# power_supply.net
KiCad netlist of a schematic drawn in EAGLE
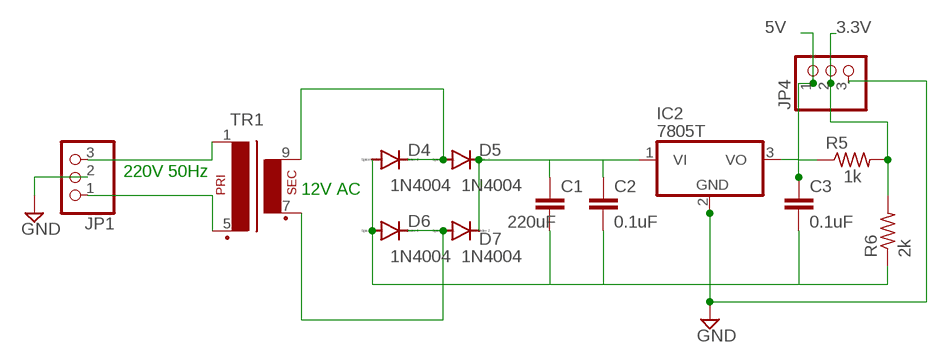
[diagram p0: schematic, sheet 1]

(export (version "E")
  (design (tool "Eeschema 10.0.6"))
  (components
    (comp (ref "C1")
      (value "220uF")
      (footprint "eagle-import:C050-025X075")
      (libsource (lib "eagle-import") (part "C-EU050-025X075"))
    )
    (comp (ref "C2")
      (value "0.1uF")
      (footprint "eagle-import:C050-025X075")
      (libsource (lib "eagle-import") (part "C-EU050-025X075"))
    )
    (comp (ref "C3")
      (value "0.1uF")
      (footprint "eagle-import:C050-025X075")
      (libsource (lib "eagle-import") (part "C-EU050-025X075"))
    )
    (comp (ref "D4")
      (value "1N4004")
      (footprint "eagle-import:DO41-10")
      (libsource (lib "eagle-import") (part "1N4004"))
    )
    (comp (ref "D5")
      (value "1N4004")
      (footprint "eagle-import:DO41-10")
      (libsource (lib "eagle-import") (part "1N4004"))
    )
    (comp (ref "D6")
      (value "1N4004")
      (footprint "eagle-import:DO41-10")
      (libsource (lib "eagle-import") (part "1N4004"))
    )
    (comp (ref "D7")
      (value "1N4004")
      (footprint "eagle-import:DO41-10")
      (libsource (lib "eagle-import") (part "1N4004"))
    )
    (comp (ref "IC2")
      (value "7805T")
      (footprint "eagle-import:TO220H")
      (libsource (lib "eagle-import") (part "78T05"))
    )
    (comp (ref "JP1")
      (value "PINHD-1X3")
      (footprint "eagle-import:1X03")
      (libsource (lib "eagle-import") (part "PINHD-1X3"))
    )
    (comp (ref "JP4")
      (value "PINHD-1X3")
      (footprint "eagle-import:1X03")
      (libsource (lib "eagle-import") (part "PINHD-1X3"))
    )
    (comp (ref "R5")
      (value "1k")
      (footprint "eagle-import:0207_10")
      (libsource (lib "eagle-import") (part "R-US_0207/10"))
    )
    (comp (ref "R6")
      (value "2k")
      (footprint "eagle-import:0207_10")
      (libsource (lib "eagle-import") (part "R-US_0207/10"))
    )
    (comp (ref "TR1")
      (value "EI30-1")
      (footprint "eagle-import:EI30-1")
      (libsource (lib "eagle-import") (part "EI30-1"))
    )
  )
  (nets
    (net (code "1") (name "/3.3V") (class "Default")
      (node (ref "JP4") (pin "2") (pinfunction "2_2") (pintype "passive"))
      (node (ref "R5") (pin "2") (pinfunction "2_2") (pintype "passive"))
      (node (ref "R6") (pin "2") (pinfunction "2_2") (pintype "passive"))
    )
    (net (code "2") (name "/5V") (class "Default")
      (node (ref "C3") (pin "1") (pinfunction "1_1") (pintype "passive"))
      (node (ref "IC2") (pin "3") (pinfunction "VO_3") (pintype "passive"))
      (node (ref "JP4") (pin "1") (pinfunction "1_1") (pintype "passive"))
      (node (ref "R5") (pin "1") (pinfunction "1_1") (pintype "passive"))
    )
    (net (code "3") (name "GND") (class "Default")
      (node (ref "C1") (pin "2") (pinfunction "2_2") (pintype "passive"))
      (node (ref "C2") (pin "2") (pinfunction "2_2") (pintype "passive"))
      (node (ref "C3") (pin "2") (pinfunction "2_2") (pintype "passive"))
      (node (ref "D4") (pin "A") (pinfunction "A_A") (pintype "passive"))
      (node (ref "D6") (pin "A") (pinfunction "A_A") (pintype "passive"))
      (node (ref "IC2") (pin "2") (pinfunction "GND_2") (pintype "passive"))
      (node (ref "JP1") (pin "2") (pinfunction "2_2") (pintype "passive"))
      (node (ref "JP4") (pin "3") (pinfunction "3_3") (pintype "passive"))
      (node (ref "R6") (pin "1") (pinfunction "1_1") (pintype "passive"))
    )
    (net (code "4") (name "Net-(IC2-VI)") (class "Default")
      (node (ref "C1") (pin "1") (pinfunction "1_1") (pintype "passive"))
      (node (ref "C2") (pin "1") (pinfunction "1_1") (pintype "passive"))
      (node (ref "D5") (pin "C") (pinfunction "C_C") (pintype "passive"))
      (node (ref "D7") (pin "C") (pinfunction "C_C") (pintype "passive"))
      (node (ref "IC2") (pin "1") (pinfunction "VI_1") (pintype "input"))
    )
    (net (code "5") (name "Net-(TR1-P1)") (class "Default")
      (node (ref "JP1") (pin "3") (pinfunction "3_3") (pintype "passive"))
      (node (ref "TR1") (pin "1") (pinfunction "P1_1") (pintype "passive"))
    )
    (net (code "6") (name "Net-(TR1-P2)") (class "Default")
      (node (ref "JP1") (pin "1") (pinfunction "1_1") (pintype "passive"))
      (node (ref "TR1") (pin "5") (pinfunction "P2_5") (pintype "passive"))
    )
    (net (code "7") (name "Net-(TR1-S3)") (class "Default")
      (node (ref "D6") (pin "C") (pinfunction "C_C") (pintype "passive"))
      (node (ref "D7") (pin "A") (pinfunction "A_A") (pintype "passive"))
      (node (ref "TR1") (pin "7") (pinfunction "S3_7") (pintype "passive"))
    )
    (net (code "8") (name "Net-(TR1-S4)") (class "Default")
      (node (ref "D4") (pin "C") (pinfunction "C_C") (pintype "passive"))
      (node (ref "D5") (pin "A") (pinfunction "A_A") (pintype "passive"))
      (node (ref "TR1") (pin "9") (pinfunction "S4_9") (pintype "passive"))
    )
  )
)
